# Sheet1.net
KiCad netlist of a schematic drawn in Altium Designer
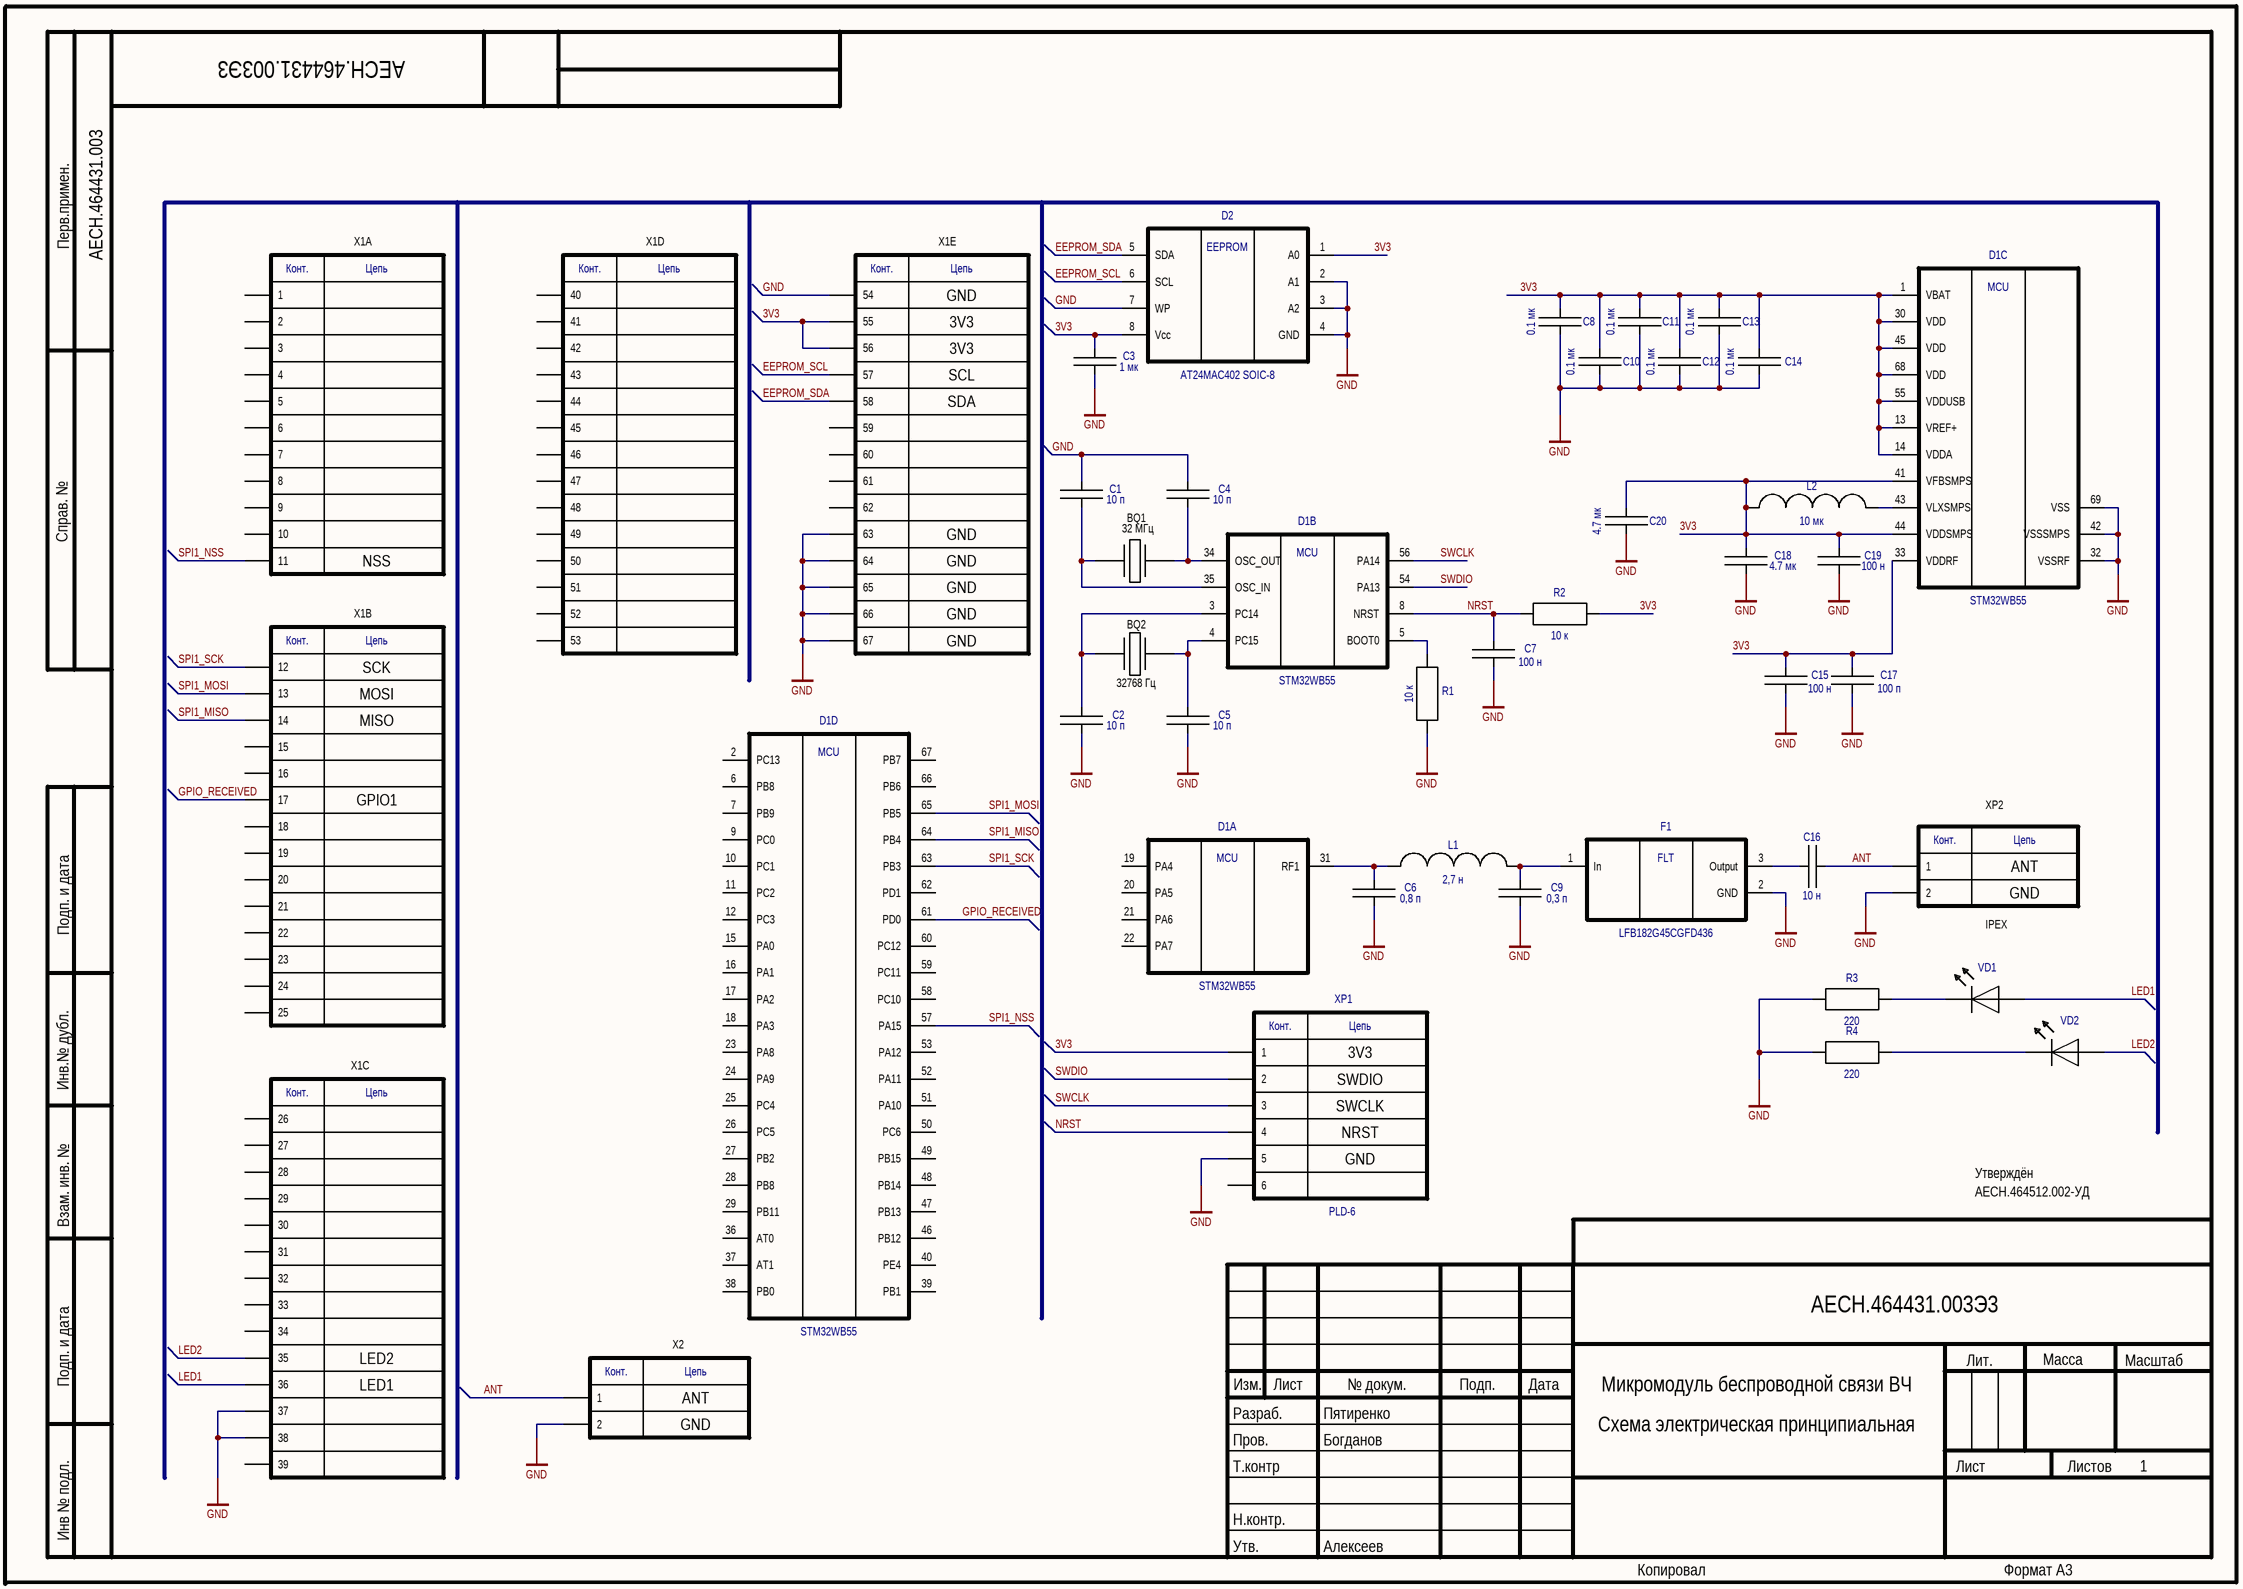
[diagram p0: Sheet1.SchDoc]

(export (version "E")
  (design (tool "Eeschema 10.0.6"))
  (components
    (comp (ref "BQ1")
      (value "32 МГц")
      (footprint "Crystal_2520")
      (fields (field (name "Comment") "Quarz"))
      (libsource (lib "Schlib1") (part "Quarz"))
    )
    (comp (ref "BQ2")
      (value "32768 Гц")
      (footprint "ABS07")
      (fields (field (name "Comment") "Quarz"))
      (libsource (lib "Schlib1") (part "Quarz"))
    )
    (comp (ref "C1")
      (value "10 п")
      (footprint "C0603")
      (fields (field (name "VOLTAGE") "?") (field (name "Comment") "C"))
      (libsource (lib "Schlib1") (part "C"))
    )
    (comp (ref "C2")
      (value "10 п")
      (footprint "C0603")
      (fields (field (name "VOLTAGE") "?") (field (name "Comment") "C"))
      (libsource (lib "Schlib1") (part "C"))
    )
    (comp (ref "C3")
      (value "1 мк")
      (footprint "C0603")
      (fields (field (name "VOLTAGE") "?") (field (name "Comment") "C"))
      (libsource (lib "Schlib1") (part "C"))
    )
    (comp (ref "C4")
      (value "10 п")
      (footprint "C0603")
      (fields (field (name "VOLTAGE") "?") (field (name "Comment") "C"))
      (libsource (lib "Schlib1") (part "C"))
    )
    (comp (ref "C5")
      (value "10 п")
      (footprint "C0603")
      (fields (field (name "VOLTAGE") "?") (field (name "Comment") "C"))
      (libsource (lib "Schlib1") (part "C"))
    )
    (comp (ref "C6")
      (value "0,8 п")
      (footprint "C0603")
      (fields (field (name "VOLTAGE") "?") (field (name "Comment") "C"))
      (libsource (lib "Schlib1") (part "C"))
    )
    (comp (ref "C7")
      (value "100 н")
      (footprint "C0603")
      (fields (field (name "VOLTAGE") "?") (field (name "Comment") "C"))
      (libsource (lib "Schlib1") (part "C"))
    )
    (comp (ref "C8")
      (value "0.1 мк")
      (footprint "C0603")
      (fields (field (name "VOLTAGE") "?") (field (name "Comment") "C"))
      (libsource (lib "Schlib1") (part "C"))
    )
    (comp (ref "C9")
      (value "0,3 п")
      (footprint "C0603")
      (fields (field (name "VOLTAGE") "?") (field (name "Comment") "C"))
      (libsource (lib "Schlib1") (part "C"))
    )
    (comp (ref "C10")
      (value "0.1 мк")
      (footprint "C0603")
      (fields (field (name "VOLTAGE") "?") (field (name "Comment") "C"))
      (libsource (lib "Schlib1") (part "C"))
    )
    (comp (ref "C11")
      (value "0.1 мк")
      (footprint "C0603")
      (fields (field (name "VOLTAGE") "?") (field (name "Comment") "C"))
      (libsource (lib "Schlib1") (part "C"))
    )
    (comp (ref "C12")
      (value "0.1 мк")
      (footprint "C0603")
      (fields (field (name "VOLTAGE") "?") (field (name "Comment") "C"))
      (libsource (lib "Schlib1") (part "C"))
    )
    (comp (ref "C13")
      (value "0.1 мк")
      (footprint "C0603")
      (fields (field (name "VOLTAGE") "?") (field (name "Comment") "C"))
      (libsource (lib "Schlib1") (part "C"))
    )
    (comp (ref "C14")
      (value "0.1 мк")
      (footprint "C0603")
      (fields (field (name "VOLTAGE") "?") (field (name "Comment") "C"))
      (libsource (lib "Schlib1") (part "C"))
    )
    (comp (ref "C15")
      (value "100 н")
      (footprint "C0603")
      (fields (field (name "VOLTAGE") "?") (field (name "Comment") "C"))
      (libsource (lib "Schlib1") (part "C"))
    )
    (comp (ref "C16")
      (value "10 н")
      (footprint "C0603")
      (fields (field (name "VOLTAGE") "?") (field (name "Comment") "C"))
      (libsource (lib "Schlib1") (part "C"))
    )
    (comp (ref "C17")
      (value "100 п")
      (footprint "C0603")
      (fields (field (name "VOLTAGE") "?") (field (name "Comment") "C"))
      (libsource (lib "Schlib1") (part "C"))
    )
    (comp (ref "C18")
      (value "4.7 мк")
      (footprint "C0603")
      (fields (field (name "VOLTAGE") "?") (field (name "Comment") "C"))
      (libsource (lib "Schlib1") (part "C"))
    )
    (comp (ref "C19")
      (value "100 н")
      (footprint "C0603")
      (fields (field (name "VOLTAGE") "?") (field (name "Comment") "C"))
      (libsource (lib "Schlib1") (part "C"))
    )
    (comp (ref "C20")
      (value "4.7 мк")
      (footprint "C0603")
      (fields (field (name "VOLTAGE") "?") (field (name "Comment") "C"))
      (libsource (lib "Schlib1") (part "C"))
    )
    (comp (ref "D1")
      (value "STM32WB55")
      (footprint "VFQFN68-8x8mm")
      (libsource (lib "Schlib1") (part "STM32WB55"))
    )
    (comp (ref "D2")
      (value "AT24MAC402 SOIC-8")
      (footprint "SOIC8")
      (libsource (lib "Schlib1") (part "AT24MAC402"))
    )
    (comp (ref "F1")
      (value "LFB182G45CGFD436")
      (footprint "0603_3pin")
      (libsource (lib "Schlib1") (part "LFB182G45CGFD436"))
    )
    (comp (ref "L1")
      (value "2,7 н")
      (footprint "INDC_0603")
      (fields (field (name "Comment") "L"))
      (libsource (lib "Schlib1") (part "L"))
    )
    (comp (ref "L2")
      (value "10 мк")
      (footprint "R0805")
      (fields (field (name "Comment") "L"))
      (libsource (lib "Schlib1") (part "L"))
    )
    (comp (ref "R1")
      (value "10 к")
      (footprint "R0603")
      (fields (field (name "Comment") "R"))
      (libsource (lib "Schlib1") (part "R"))
    )
    (comp (ref "R2")
      (value "10 к")
      (footprint "R0603")
      (fields (field (name "Comment") "R"))
      (libsource (lib "Schlib1") (part "R"))
    )
    (comp (ref "R3")
      (value "220")
      (footprint "R0603")
      (fields (field (name "Comment") "R"))
      (libsource (lib "Schlib1") (part "R"))
    )
    (comp (ref "R4")
      (value "220")
      (footprint "R0603")
      (fields (field (name "Comment") "R"))
      (libsource (lib "Schlib1") (part "R"))
    )
    (comp (ref "VD1")
      (value "LED")
      (footprint "LED_0805")
      (fields (field (name "VOLTAGE") "?"))
      (libsource (lib "Schlib1") (part "VD_LED"))
    )
    (comp (ref "VD2")
      (value "LED")
      (footprint "LED_0805")
      (fields (field (name "VOLTAGE") "?"))
      (libsource (lib "Schlib1") (part "VD_LED"))
    )
    (comp (ref "X1")
      (value "M.2 - 1-2199230-4")
      (footprint "M.2 - 1-2199230-4 EDGE")
      (libsource (lib "Schlib1") (part "M.2"))
    )
    (comp (ref "X2") (value "~") (footprint "SMA_kont") (libsource (lib "Schlib1") (part "2pin")))
    (comp (ref "XP1")
      (value "PLD-6")
      (footprint "PLD-6")
      (fields (field (name "PARTNUMBER") "PLD-6"))
      (libsource (lib "Schlib1") (part "6pin"))
    )
    (comp (ref "XP2") (value "IPEX") (footprint "IPEX") (libsource (lib "Schlib1") (part "2pin")))
  )
  (nets
    (net (code "1") (name "/3V3") (class "Default")
      (node (ref "C10") (pin "1") (pinfunction "1_1") (pintype "passive"))
      (node (ref "C11") (pin "1") (pinfunction "1_1") (pintype "passive"))
      (node (ref "C12") (pin "1") (pinfunction "1_1") (pintype "passive"))
      (node (ref "C13") (pin "1") (pinfunction "1_1") (pintype "passive"))
      (node (ref "C14") (pin "1") (pinfunction "1_1") (pintype "passive"))
      (node (ref "C15") (pin "1") (pinfunction "1_1") (pintype "passive"))
      (node (ref "C17") (pin "1") (pinfunction "1_1") (pintype "passive"))
      (node (ref "C18") (pin "1") (pinfunction "1_1") (pintype "passive"))
      (node (ref "C19") (pin "1") (pinfunction "1_1") (pintype "passive"))
      (node (ref "C20") (pin "1") (pinfunction "1_1") (pintype "passive"))
      (node (ref "C3") (pin "1") (pinfunction "1_1") (pintype "passive"))
      (node (ref "C8") (pin "1") (pinfunction "1_1") (pintype "passive"))
      (node (ref "D1") (pin "1") (pinfunction "VBAT_1") (pintype "passive"))
      (node (ref "D1") (pin "13") (pinfunction "VREF+_13") (pintype "passive"))
      (node (ref "D1") (pin "14") (pinfunction "VDDA_14") (pintype "passive"))
      (node (ref "D1") (pin "30") (pinfunction "VDD_30") (pintype "passive"))
      (node (ref "D1") (pin "33") (pinfunction "VDDRF_33") (pintype "passive"))
      (node (ref "D1") (pin "41") (pinfunction "VFBSMPS_41") (pintype "passive"))
      (node (ref "D1") (pin "44") (pinfunction "VDDSMPS_44") (pintype "passive"))
      (node (ref "D1") (pin "45") (pinfunction "VDD_45") (pintype "passive"))
      (node (ref "D1") (pin "55") (pinfunction "VDDUSB_55") (pintype "passive"))
      (node (ref "D1") (pin "68") (pinfunction "VDD_68") (pintype "passive"))
      (node (ref "D2") (pin "1") (pinfunction "A0_1") (pintype "passive"))
      (node (ref "D2") (pin "8") (pinfunction "Vcc_8") (pintype "passive"))
      (node (ref "L2") (pin "1") (pinfunction "1_1") (pintype "passive"))
      (node (ref "R2") (pin "1") (pinfunction "1_1") (pintype "passive"))
      (node (ref "X1") (pin "55") (pinfunction "55_55") (pintype "passive"))
      (node (ref "X1") (pin "56") (pinfunction "56_56") (pintype "passive"))
      (node (ref "XP1") (pin "1") (pinfunction "1_1") (pintype "passive"))
    )
    (net (code "2") (name "/ANT") (class "Default")
      (node (ref "C16") (pin "2") (pinfunction "2_2") (pintype "passive"))
      (node (ref "X2") (pin "1") (pinfunction "1_1") (pintype "passive"))
      (node (ref "XP2") (pin "1") (pinfunction "1_1") (pintype "passive"))
    )
    (net (code "3") (name "/EEPROM_SCL") (class "Default")
      (node (ref "D2") (pin "6") (pinfunction "SCL_6") (pintype "passive"))
      (node (ref "X1") (pin "57") (pinfunction "57_57") (pintype "passive"))
    )
    (net (code "4") (name "/EEPROM_SDA") (class "Default")
      (node (ref "D2") (pin "5") (pinfunction "SDA_5") (pintype "passive"))
      (node (ref "X1") (pin "58") (pinfunction "58_58") (pintype "passive"))
    )
    (net (code "5") (name "/GPIO_RECEIVED") (class "Default")
      (node (ref "D1") (pin "61") (pinfunction "PD0_61") (pintype "passive"))
      (node (ref "X1") (pin "17") (pinfunction "17_17") (pintype "passive"))
    )
    (net (code "6") (name "/LED1") (class "Default")
      (node (ref "VD1") (pin "1") (pinfunction "1_1") (pintype "passive"))
      (node (ref "X1") (pin "36") (pinfunction "36_36") (pintype "passive"))
    )
    (net (code "7") (name "/LED2") (class "Default")
      (node (ref "VD2") (pin "1") (pinfunction "1_1") (pintype "passive"))
      (node (ref "X1") (pin "35") (pinfunction "35_35") (pintype "passive"))
    )
    (net (code "8") (name "/NRST") (class "Default")
      (node (ref "C7") (pin "1") (pinfunction "1_1") (pintype "passive"))
      (node (ref "D1") (pin "8") (pinfunction "NRST_8") (pintype "passive"))
      (node (ref "R2") (pin "2") (pinfunction "2_2") (pintype "passive"))
      (node (ref "XP1") (pin "4") (pinfunction "4_4") (pintype "passive"))
    )
    (net (code "9") (name "/SPI1_MISO") (class "Default")
      (node (ref "D1") (pin "64") (pinfunction "PB4_64") (pintype "passive"))
      (node (ref "X1") (pin "14") (pinfunction "14_14") (pintype "passive"))
    )
    (net (code "10") (name "/SPI1_MOSI") (class "Default")
      (node (ref "D1") (pin "65") (pinfunction "PB5_65") (pintype "passive"))
      (node (ref "X1") (pin "13") (pinfunction "13_13") (pintype "passive"))
    )
    (net (code "11") (name "/SPI1_NSS") (class "Default")
      (node (ref "D1") (pin "57") (pinfunction "PA15_57") (pintype "passive"))
      (node (ref "X1") (pin "11") (pinfunction "11_11") (pintype "passive"))
    )
    (net (code "12") (name "/SPI1_SCK") (class "Default")
      (node (ref "D1") (pin "63") (pinfunction "PB3_63") (pintype "passive"))
      (node (ref "X1") (pin "12") (pinfunction "12_12") (pintype "passive"))
    )
    (net (code "13") (name "/SWCLK") (class "Default")
      (node (ref "D1") (pin "56") (pinfunction "PA14_56") (pintype "passive"))
      (node (ref "XP1") (pin "3") (pinfunction "3_3") (pintype "passive"))
    )
    (net (code "14") (name "/SWDIO") (class "Default")
      (node (ref "D1") (pin "54") (pinfunction "PA13_54") (pintype "passive"))
      (node (ref "XP1") (pin "2") (pinfunction "2_2") (pintype "passive"))
    )
    (net (code "15") (name "GND") (class "Default")
      (node (ref "C1") (pin "1") (pinfunction "1_1") (pintype "passive"))
      (node (ref "C10") (pin "2") (pinfunction "2_2") (pintype "passive"))
      (node (ref "C11") (pin "2") (pinfunction "2_2") (pintype "passive"))
      (node (ref "C12") (pin "2") (pinfunction "2_2") (pintype "passive"))
      (node (ref "C13") (pin "2") (pinfunction "2_2") (pintype "passive"))
      (node (ref "C14") (pin "2") (pinfunction "2_2") (pintype "passive"))
      (node (ref "C15") (pin "2") (pinfunction "2_2") (pintype "passive"))
      (node (ref "C17") (pin "2") (pinfunction "2_2") (pintype "passive"))
      (node (ref "C18") (pin "2") (pinfunction "2_2") (pintype "passive"))
      (node (ref "C19") (pin "2") (pinfunction "2_2") (pintype "passive"))
      (node (ref "C2") (pin "2") (pinfunction "2_2") (pintype "passive"))
      (node (ref "C20") (pin "2") (pinfunction "2_2") (pintype "passive"))
      (node (ref "C3") (pin "2") (pinfunction "2_2") (pintype "passive"))
      (node (ref "C4") (pin "1") (pinfunction "1_1") (pintype "passive"))
      (node (ref "C5") (pin "2") (pinfunction "2_2") (pintype "passive"))
      (node (ref "C6") (pin "2") (pinfunction "2_2") (pintype "passive"))
      (node (ref "C7") (pin "2") (pinfunction "2_2") (pintype "passive"))
      (node (ref "C8") (pin "2") (pinfunction "2_2") (pintype "passive"))
      (node (ref "C9") (pin "2") (pinfunction "2_2") (pintype "passive"))
      (node (ref "D1") (pin "32") (pinfunction "VSSRF_32") (pintype "passive"))
      (node (ref "D1") (pin "42") (pinfunction "VSSSMPS_42") (pintype "passive"))
      (node (ref "D1") (pin "69") (pinfunction "VSS_69") (pintype "passive"))
      (node (ref "D2") (pin "2") (pinfunction "A1_2") (pintype "passive"))
      (node (ref "D2") (pin "3") (pinfunction "A2_3") (pintype "passive"))
      (node (ref "D2") (pin "4") (pinfunction "GND_4") (pintype "passive"))
      (node (ref "D2") (pin "7") (pinfunction "WP_7") (pintype "passive"))
      (node (ref "F1") (pin "2") (pinfunction "GND_2") (pintype "passive"))
      (node (ref "R1") (pin "1") (pinfunction "1_1") (pintype "passive"))
      (node (ref "R3") (pin "2") (pinfunction "2_2") (pintype "passive"))
      (node (ref "R4") (pin "2") (pinfunction "2_2") (pintype "passive"))
      (node (ref "X1") (pin "37") (pinfunction "37_37") (pintype "passive"))
      (node (ref "X1") (pin "38") (pinfunction "38_38") (pintype "passive"))
      (node (ref "X1") (pin "54") (pinfunction "54_54") (pintype "passive"))
      (node (ref "X1") (pin "63") (pinfunction "63_63") (pintype "passive"))
      (node (ref "X1") (pin "64") (pinfunction "64_64") (pintype "passive"))
      (node (ref "X1") (pin "65") (pinfunction "65_65") (pintype "passive"))
      (node (ref "X1") (pin "66") (pinfunction "66_66") (pintype "passive"))
      (node (ref "X1") (pin "67") (pinfunction "67_67") (pintype "passive"))
      (node (ref "X2") (pin "2") (pinfunction "2_2") (pintype "passive"))
      (node (ref "XP1") (pin "5") (pinfunction "5_5") (pintype "passive"))
      (node (ref "XP2") (pin "2") (pinfunction "2_2") (pintype "passive"))
    )
    (net (code "16") (name "Net-(D1A-RF1)") (class "Default")
      (node (ref "C6") (pin "1") (pinfunction "1_1") (pintype "passive"))
      (node (ref "D1") (pin "31") (pinfunction "RF1_31") (pintype "passive"))
      (node (ref "L1") (pin "1") (pinfunction "1_1") (pintype "passive"))
    )
    (net (code "17") (name "Net-(D1B-BOOT0)") (class "Default")
      (node (ref "D1") (pin "5") (pinfunction "BOOT0_5") (pintype "passive"))
      (node (ref "R1") (pin "2") (pinfunction "2_2") (pintype "passive"))
    )
    (net (code "18") (name "Net-(D1B-OSC_IN)") (class "Default")
      (node (ref "BQ1") (pin "1") (pintype "passive"))
      (node (ref "C1") (pin "2") (pinfunction "2_2") (pintype "passive"))
      (node (ref "D1") (pin "35") (pinfunction "OSC_IN_35") (pintype "passive"))
    )
    (net (code "19") (name "Net-(D1B-OSC_OUT)") (class "Default")
      (node (ref "BQ1") (pin "2") (pintype "passive"))
      (node (ref "C4") (pin "2") (pinfunction "2_2") (pintype "passive"))
      (node (ref "D1") (pin "34") (pinfunction "OSC_OUT_34") (pintype "passive"))
    )
    (net (code "20") (name "Net-(D1B-PC14)") (class "Default")
      (node (ref "BQ2") (pin "1") (pintype "passive"))
      (node (ref "C2") (pin "1") (pinfunction "1_1") (pintype "passive"))
      (node (ref "D1") (pin "3") (pinfunction "PC14_3") (pintype "passive"))
    )
    (net (code "21") (name "Net-(D1B-PC15)") (class "Default")
      (node (ref "BQ2") (pin "2") (pintype "passive"))
      (node (ref "C5") (pin "1") (pinfunction "1_1") (pintype "passive"))
      (node (ref "D1") (pin "4") (pinfunction "PC15_4") (pintype "passive"))
    )
    (net (code "22") (name "Net-(D1C-VLXSMPS)") (class "Default")
      (node (ref "D1") (pin "43") (pinfunction "VLXSMPS_43") (pintype "passive"))
      (node (ref "L2") (pin "2") (pinfunction "2_2") (pintype "passive"))
    )
    (net (code "23") (name "Net-(F1-In)") (class "Default")
      (node (ref "C9") (pin "1") (pinfunction "1_1") (pintype "passive"))
      (node (ref "F1") (pin "1") (pinfunction "In_1") (pintype "passive"))
      (node (ref "L1") (pin "2") (pinfunction "2_2") (pintype "passive"))
    )
    (net (code "24") (name "Net-(F1-Output)") (class "Default")
      (node (ref "C16") (pin "1") (pinfunction "1_1") (pintype "passive"))
      (node (ref "F1") (pin "3") (pinfunction "Output_3") (pintype "passive"))
    )
    (net (code "25") (name "Net-(R3-Pad1)") (class "Default")
      (node (ref "R3") (pin "1") (pinfunction "1_1") (pintype "passive"))
      (node (ref "VD1") (pin "2") (pinfunction "2_2") (pintype "passive"))
    )
    (net (code "26") (name "Net-(R4-Pad1)") (class "Default")
      (node (ref "R4") (pin "1") (pinfunction "1_1") (pintype "passive"))
      (node (ref "VD2") (pin "2") (pinfunction "2_2") (pintype "passive"))
    )
    (net (code "27") (name "unconnected-(D1A-PA4-Pad19)") (class "Default")
      (node (ref "D1") (pin "19") (pinfunction "PA4_19") (pintype "passive"))
    )
    (net (code "28") (name "unconnected-(D1A-PA5-Pad20)") (class "Default")
      (node (ref "D1") (pin "20") (pinfunction "PA5_20") (pintype "passive"))
    )
    (net (code "29") (name "unconnected-(D1A-PA6-Pad21)") (class "Default")
      (node (ref "D1") (pin "21") (pinfunction "PA6_21") (pintype "passive"))
    )
    (net (code "30") (name "unconnected-(D1A-PA7-Pad22)") (class "Default")
      (node (ref "D1") (pin "22") (pinfunction "PA7_22") (pintype "passive"))
    )
    (net (code "31") (name "unconnected-(D1D-AT0-Pad36)") (class "Default")
      (node (ref "D1") (pin "36") (pinfunction "AT0_36") (pintype "passive"))
    )
    (net (code "32") (name "unconnected-(D1D-AT1-Pad37)") (class "Default")
      (node (ref "D1") (pin "37") (pinfunction "AT1_37") (pintype "passive"))
    )
    (net (code "33") (name "unconnected-(D1D-PA0-Pad15)") (class "Default")
      (node (ref "D1") (pin "15") (pinfunction "PA0_15") (pintype "passive"))
    )
    (net (code "34") (name "unconnected-(D1D-PA1-Pad16)") (class "Default")
      (node (ref "D1") (pin "16") (pinfunction "PA1_16") (pintype "passive"))
    )
    (net (code "35") (name "unconnected-(D1D-PA2-Pad17)") (class "Default")
      (node (ref "D1") (pin "17") (pinfunction "PA2_17") (pintype "passive"))
    )
    (net (code "36") (name "unconnected-(D1D-PA3-Pad18)") (class "Default")
      (node (ref "D1") (pin "18") (pinfunction "PA3_18") (pintype "passive"))
    )
    (net (code "37") (name "unconnected-(D1D-PA8-Pad23)") (class "Default")
      (node (ref "D1") (pin "23") (pinfunction "PA8_23") (pintype "passive"))
    )
    (net (code "38") (name "unconnected-(D1D-PA9-Pad24)") (class "Default")
      (node (ref "D1") (pin "24") (pinfunction "PA9_24") (pintype "passive"))
    )
    (net (code "39") (name "unconnected-(D1D-PA10-Pad51)") (class "Default")
      (node (ref "D1") (pin "51") (pinfunction "PA10_51") (pintype "passive"))
    )
    (net (code "40") (name "unconnected-(D1D-PA11-Pad52)") (class "Default")
      (node (ref "D1") (pin "52") (pinfunction "PA11_52") (pintype "passive"))
    )
    (net (code "41") (name "unconnected-(D1D-PA12-Pad53)") (class "Default")
      (node (ref "D1") (pin "53") (pinfunction "PA12_53") (pintype "passive"))
    )
    (net (code "42") (name "unconnected-(D1D-PB0-Pad38)") (class "Default")
      (node (ref "D1") (pin "38") (pinfunction "PB0_38") (pintype "passive"))
    )
    (net (code "43") (name "unconnected-(D1D-PB1-Pad39)") (class "Default")
      (node (ref "D1") (pin "39") (pinfunction "PB1_39") (pintype "passive"))
    )
    (net (code "44") (name "unconnected-(D1D-PB2-Pad27)") (class "Default")
      (node (ref "D1") (pin "27") (pinfunction "PB2_27") (pintype "passive"))
    )
    (net (code "45") (name "unconnected-(D1D-PB6-Pad66)") (class "Default")
      (node (ref "D1") (pin "66") (pinfunction "PB6_66") (pintype "passive"))
    )
    (net (code "46") (name "unconnected-(D1D-PB7-Pad67)") (class "Default")
      (node (ref "D1") (pin "67") (pinfunction "PB7_67") (pintype "passive"))
    )
    (net (code "47") (name "unconnected-(D1D-PB8-Pad6)") (class "Default")
      (node (ref "D1") (pin "6") (pinfunction "PB8_6") (pintype "passive"))
    )
    (net (code "48") (name "unconnected-(D1D-PB8-Pad28)") (class "Default")
      (node (ref "D1") (pin "28") (pinfunction "PB8_28") (pintype "passive"))
    )
    (net (code "49") (name "unconnected-(D1D-PB9-Pad7)") (class "Default")
      (node (ref "D1") (pin "7") (pinfunction "PB9_7") (pintype "passive"))
    )
    (net (code "50") (name "unconnected-(D1D-PB11-Pad29)") (class "Default")
      (node (ref "D1") (pin "29") (pinfunction "PB11_29") (pintype "passive"))
    )
    (net (code "51") (name "unconnected-(D1D-PB12-Pad46)") (class "Default")
      (node (ref "D1") (pin "46") (pinfunction "PB12_46") (pintype "passive"))
    )
    (net (code "52") (name "unconnected-(D1D-PB13-Pad47)") (class "Default")
      (node (ref "D1") (pin "47") (pinfunction "PB13_47") (pintype "passive"))
    )
    (net (code "53") (name "unconnected-(D1D-PB14-Pad48)") (class "Default")
      (node (ref "D1") (pin "48") (pinfunction "PB14_48") (pintype "passive"))
    )
    (net (code "54") (name "unconnected-(D1D-PB15-Pad49)") (class "Default")
      (node (ref "D1") (pin "49") (pinfunction "PB15_49") (pintype "passive"))
    )
    (net (code "55") (name "unconnected-(D1D-PC0-Pad9)") (class "Default")
      (node (ref "D1") (pin "9") (pinfunction "PC0_9") (pintype "passive"))
    )
    (net (code "56") (name "unconnected-(D1D-PC1-Pad10)") (class "Default")
      (node (ref "D1") (pin "10") (pinfunction "PC1_10") (pintype "passive"))
    )
    (net (code "57") (name "unconnected-(D1D-PC2-Pad11)") (class "Default")
      (node (ref "D1") (pin "11") (pinfunction "PC2_11") (pintype "passive"))
    )
    (net (code "58") (name "unconnected-(D1D-PC3-Pad12)") (class "Default")
      (node (ref "D1") (pin "12") (pinfunction "PC3_12") (pintype "passive"))
    )
    (net (code "59") (name "unconnected-(D1D-PC4-Pad25)") (class "Default")
      (node (ref "D1") (pin "25") (pinfunction "PC4_25") (pintype "passive"))
    )
    (net (code "60") (name "unconnected-(D1D-PC5-Pad26)") (class "Default")
      (node (ref "D1") (pin "26") (pinfunction "PC5_26") (pintype "passive"))
    )
    (net (code "61") (name "unconnected-(D1D-PC6-Pad50)") (class "Default")
      (node (ref "D1") (pin "50") (pinfunction "PC6_50") (pintype "passive"))
    )
    (net (code "62") (name "unconnected-(D1D-PC10-Pad58)") (class "Default")
      (node (ref "D1") (pin "58") (pinfunction "PC10_58") (pintype "passive"))
    )
    (net (code "63") (name "unconnected-(D1D-PC11-Pad59)") (class "Default")
      (node (ref "D1") (pin "59") (pinfunction "PC11_59") (pintype "passive"))
    )
    (net (code "64") (name "unconnected-(D1D-PC12-Pad60)") (class "Default")
      (node (ref "D1") (pin "60") (pinfunction "PC12_60") (pintype "passive"))
    )
    (net (code "65") (name "unconnected-(D1D-PC13-Pad2)") (class "Default")
      (node (ref "D1") (pin "2") (pinfunction "PC13_2") (pintype "passive"))
    )
    (net (code "66") (name "unconnected-(D1D-PD1-Pad62)") (class "Default")
      (node (ref "D1") (pin "62") (pinfunction "PD1_62") (pintype "passive"))
    )
    (net (code "67") (name "unconnected-(D1D-PE4-Pad40)") (class "Default")
      (node (ref "D1") (pin "40") (pinfunction "PE4_40") (pintype "passive"))
    )
    (net (code "68") (name "unconnected-(X1-Pad1)") (class "Default")
      (node (ref "X1") (pin "1") (pinfunction "1_1") (pintype "passive"))
    )
    (net (code "69") (name "unconnected-(X1-Pad2)") (class "Default")
      (node (ref "X1") (pin "2") (pinfunction "2_2") (pintype "passive"))
    )
    (net (code "70") (name "unconnected-(X1-Pad3)") (class "Default")
      (node (ref "X1") (pin "3") (pinfunction "3_3") (pintype "passive"))
    )
    (net (code "71") (name "unconnected-(X1-Pad4)") (class "Default")
      (node (ref "X1") (pin "4") (pinfunction "4_4") (pintype "passive"))
    )
    (net (code "72") (name "unconnected-(X1-Pad5)") (class "Default")
      (node (ref "X1") (pin "5") (pinfunction "5_5") (pintype "passive"))
    )
    (net (code "73") (name "unconnected-(X1-Pad6)") (class "Default")
      (node (ref "X1") (pin "6") (pinfunction "6_6") (pintype "passive"))
    )
    (net (code "74") (name "unconnected-(X1-Pad7)") (class "Default")
      (node (ref "X1") (pin "7") (pinfunction "7_7") (pintype "passive"))
    )
    (net (code "75") (name "unconnected-(X1-Pad8)") (class "Default")
      (node (ref "X1") (pin "8") (pinfunction "8_8") (pintype "passive"))
    )
    (net (code "76") (name "unconnected-(X1-Pad9)") (class "Default")
      (node (ref "X1") (pin "9") (pinfunction "9_9") (pintype "passive"))
    )
    (net (code "77") (name "unconnected-(X1-Pad10)") (class "Default")
      (node (ref "X1") (pin "10") (pinfunction "10_10") (pintype "passive"))
    )
    (net (code "78") (name "unconnected-(X1-Pad15)") (class "Default")
      (node (ref "X1") (pin "15") (pinfunction "15_15") (pintype "passive"))
    )
    (net (code "79") (name "unconnected-(X1-Pad16)") (class "Default")
      (node (ref "X1") (pin "16") (pinfunction "16_16") (pintype "passive"))
    )
    (net (code "80") (name "unconnected-(X1-Pad18)") (class "Default")
      (node (ref "X1") (pin "18") (pinfunction "18_18") (pintype "passive"))
    )
    (net (code "81") (name "unconnected-(X1-Pad19)") (class "Default")
      (node (ref "X1") (pin "19") (pinfunction "19_19") (pintype "passive"))
    )
    (net (code "82") (name "unconnected-(X1-Pad20)") (class "Default")
      (node (ref "X1") (pin "20") (pinfunction "20_20") (pintype "passive"))
    )
    (net (code "83") (name "unconnected-(X1-Pad21)") (class "Default")
      (node (ref "X1") (pin "21") (pinfunction "21_21") (pintype "passive"))
    )
    (net (code "84") (name "unconnected-(X1-Pad22)") (class "Default")
      (node (ref "X1") (pin "22") (pinfunction "22_22") (pintype "passive"))
    )
    (net (code "85") (name "unconnected-(X1-Pad23)") (class "Default")
      (node (ref "X1") (pin "23") (pinfunction "23_23") (pintype "passive"))
    )
    (net (code "86") (name "unconnected-(X1-Pad24)") (class "Default")
      (node (ref "X1") (pin "24") (pinfunction "24_24") (pintype "passive"))
    )
    (net (code "87") (name "unconnected-(X1-Pad25)") (class "Default")
      (node (ref "X1") (pin "25") (pinfunction "25_25") (pintype "passive"))
    )
    (net (code "88") (name "unconnected-(X1-Pad26)") (class "Default")
      (node (ref "X1") (pin "26") (pinfunction "26_26") (pintype "passive"))
    )
    (net (code "89") (name "unconnected-(X1-Pad27)") (class "Default")
      (node (ref "X1") (pin "27") (pinfunction "27_27") (pintype "passive"))
    )
    (net (code "90") (name "unconnected-(X1-Pad28)") (class "Default")
      (node (ref "X1") (pin "28") (pinfunction "28_28") (pintype "passive"))
    )
    (net (code "91") (name "unconnected-(X1-Pad29)") (class "Default")
      (node (ref "X1") (pin "29") (pinfunction "29_29") (pintype "passive"))
    )
    (net (code "92") (name "unconnected-(X1-Pad30)") (class "Default")
      (node (ref "X1") (pin "30") (pinfunction "30_30") (pintype "passive"))
    )
    (net (code "93") (name "unconnected-(X1-Pad31)") (class "Default")
      (node (ref "X1") (pin "31") (pinfunction "31_31") (pintype "passive"))
    )
    (net (code "94") (name "unconnected-(X1-Pad32)") (class "Default")
      (node (ref "X1") (pin "32") (pinfunction "32_32") (pintype "passive"))
    )
    (net (code "95") (name "unconnected-(X1-Pad33)") (class "Default")
      (node (ref "X1") (pin "33") (pinfunction "33_33") (pintype "passive"))
    )
    (net (code "96") (name "unconnected-(X1-Pad34)") (class "Default")
      (node (ref "X1") (pin "34") (pinfunction "34_34") (pintype "passive"))
    )
    (net (code "97") (name "unconnected-(X1-Pad39)") (class "Default")
      (node (ref "X1") (pin "39") (pinfunction "39_39") (pintype "passive"))
    )
    (net (code "98") (name "unconnected-(X1-Pad40)") (class "Default")
      (node (ref "X1") (pin "40") (pinfunction "40_40") (pintype "passive"))
    )
    (net (code "99") (name "unconnected-(X1-Pad41)") (class "Default")
      (node (ref "X1") (pin "41") (pinfunction "41_41") (pintype "passive"))
    )
    (net (code "100") (name "unconnected-(X1-Pad42)") (class "Default")
      (node (ref "X1") (pin "42") (pinfunction "42_42") (pintype "passive"))
    )
    (net (code "101") (name "unconnected-(X1-Pad43)") (class "Default")
      (node (ref "X1") (pin "43") (pinfunction "43_43") (pintype "passive"))
    )
    (net (code "102") (name "unconnected-(X1-Pad44)") (class "Default")
      (node (ref "X1") (pin "44") (pinfunction "44_44") (pintype "passive"))
    )
    (net (code "103") (name "unconnected-(X1-Pad45)") (class "Default")
      (node (ref "X1") (pin "45") (pinfunction "45_45") (pintype "passive"))
    )
    (net (code "104") (name "unconnected-(X1-Pad46)") (class "Default")
      (node (ref "X1") (pin "46") (pinfunction "46_46") (pintype "passive"))
    )
    (net (code "105") (name "unconnected-(X1-Pad47)") (class "Default")
      (node (ref "X1") (pin "47") (pinfunction "47_47") (pintype "passive"))
    )
    (net (code "106") (name "unconnected-(X1-Pad48)") (class "Default")
      (node (ref "X1") (pin "48") (pinfunction "48_48") (pintype "passive"))
    )
    (net (code "107") (name "unconnected-(X1-Pad49)") (class "Default")
      (node (ref "X1") (pin "49") (pinfunction "49_49") (pintype "passive"))
    )
    (net (code "108") (name "unconnected-(X1-Pad50)") (class "Default")
      (node (ref "X1") (pin "50") (pinfunction "50_50") (pintype "passive"))
    )
    (net (code "109") (name "unconnected-(X1-Pad51)") (class "Default")
      (node (ref "X1") (pin "51") (pinfunction "51_51") (pintype "passive"))
    )
    (net (code "110") (name "unconnected-(X1-Pad52)") (class "Default")
      (node (ref "X1") (pin "52") (pinfunction "52_52") (pintype "passive"))
    )
    (net (code "111") (name "unconnected-(X1-Pad53)") (class "Default")
      (node (ref "X1") (pin "53") (pinfunction "53_53") (pintype "passive"))
    )
    (net (code "112") (name "unconnected-(X1-Pad59)") (class "Default")
      (node (ref "X1") (pin "59") (pinfunction "59_59") (pintype "passive"))
    )
    (net (code "113") (name "unconnected-(X1-Pad60)") (class "Default")
      (node (ref "X1") (pin "60") (pinfunction "60_60") (pintype "passive"))
    )
    (net (code "114") (name "unconnected-(X1-Pad61)") (class "Default")
      (node (ref "X1") (pin "61") (pinfunction "61_61") (pintype "passive"))
    )
    (net (code "115") (name "unconnected-(X1-Pad62)") (class "Default")
      (node (ref "X1") (pin "62") (pinfunction "62_62") (pintype "passive"))
    )
    (net (code "116") (name "unconnected-(XP1-Pad6)") (class "Default")
      (node (ref "XP1") (pin "6") (pinfunction "6_6") (pintype "passive"))
    )
  )
)
